# USB.net
KiCad netlist of a schematic drawn in Altium Designer
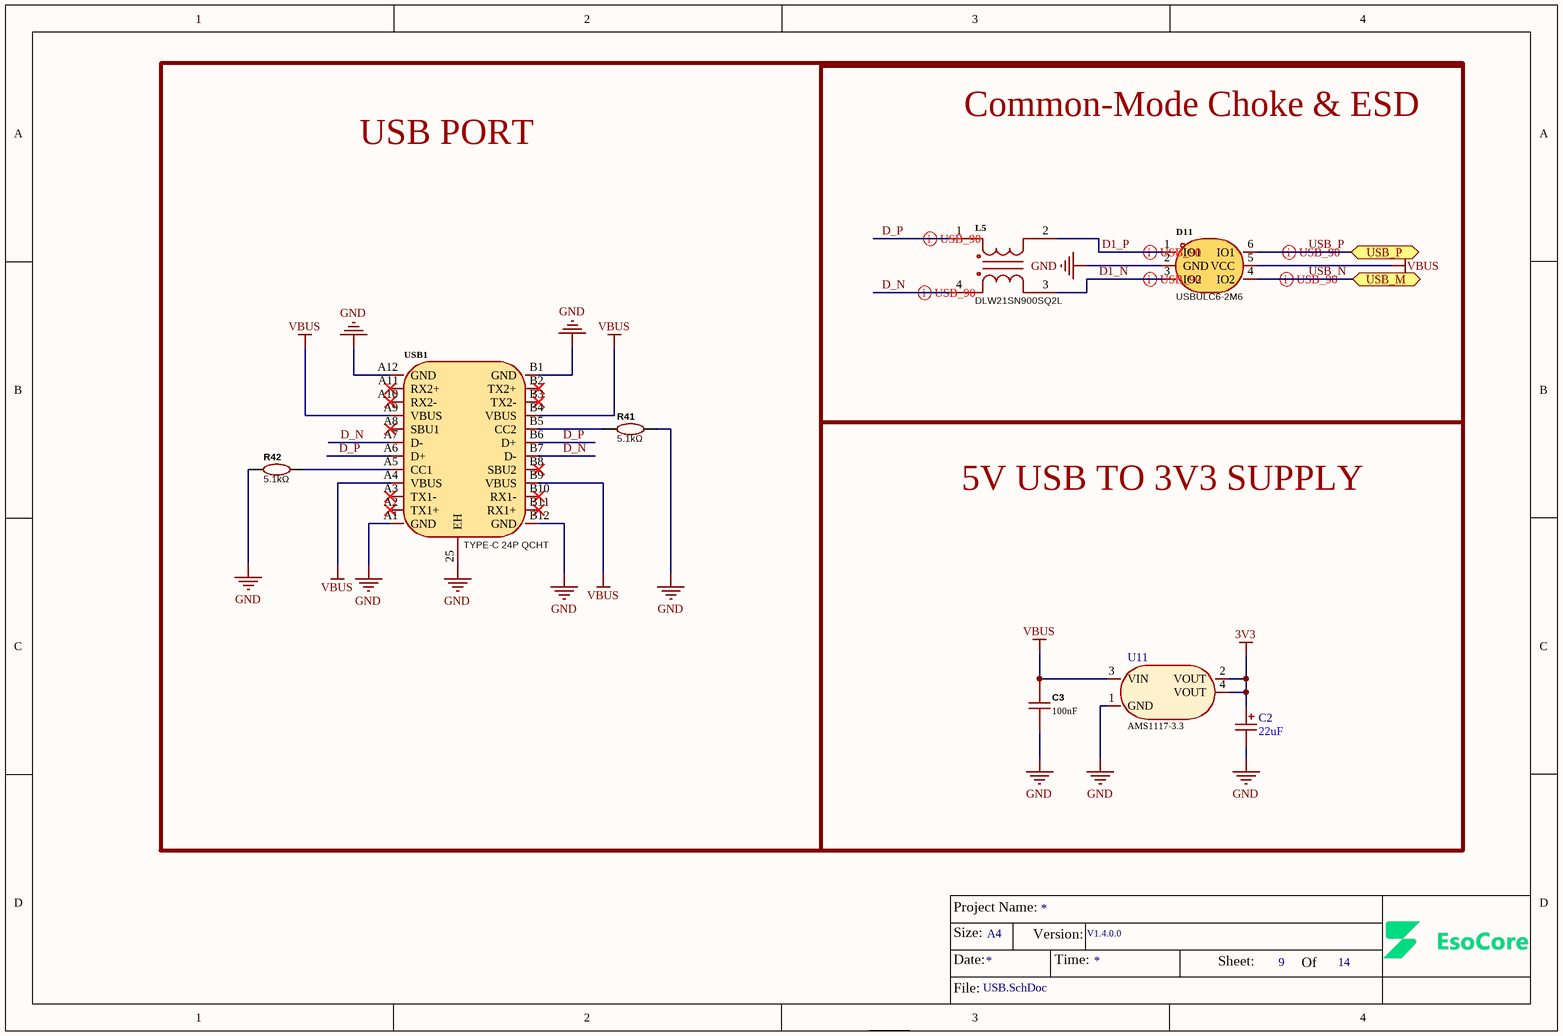
[diagram p0: USB.SchDoc]

(export (version "E")
  (design (tool "Eeschema 10.0.6"))
  (components
    (comp (ref "C2")
      (value "22uF")
      (footprint "CASE-A_3216")
      (fields
        (field (name "MANUFACTURER") "Kyocera AVX")
        (field (name "MANUFACTURER PART") "TAJA226K010RNJ")
        (field (name "TOLERANCE") "±10%")
      )
      (libsource (lib "altium-import") (part "root_1_TAJA226K010RNJ_"))
    )
    (comp (ref "C3")
      (value "100nF")
      (footprint "C_0603")
      (fields
        (field (name "MANUFACTURER") "YAGEO(国巨)")
        (field (name "MANUFACTURER PART") "CC0603KRX7R9BB104")
        (field (name "TOLERANCE") "±10%")
      )
      (libsource (lib "altium-import") (part "root_3_CC0603KRX7R9BB104_"))
    )
    (comp (ref "D11")
      (value "USBULC6-2M6")
      (footprint "SON-6_L1.4-W1.0-P0.50-TL_USBULC6-2M6")
      (fields (field (name "MANUFACTURER") "ST(意法半导体)"))
      (libsource (lib "EsoCore_Edge_Board_V1-0.0.0") (part "USBULC6-2M6"))
    )
    (comp (ref "L5")
      (value "DLW21SN900SQ2L")
      (footprint "FILTER-SMD_4P-L2.0-W1.2-BL_DLW21H")
      (fields (field (name "MANUFACTURER") "muRata(村田)"))
      (libsource (lib "EsoCore_Edge_Board_V1-0.0.0") (part "DLW21SN900SQ2L"))
    )
    (comp (ref "R41")
      (value "5.1kΩ")
      (footprint "R_0603")
      (fields (field (name "MANUFACTURER") "YAGEO(国巨)") (field (name "MANUFACTURER PART") "RC0603FR-075K1L"))
      (libsource (lib "altium-import") (part "root_0_5.1kΩ_"))
    )
    (comp (ref "R42")
      (value "5.1kΩ")
      (footprint "R_0603")
      (fields (field (name "MANUFACTURER") "YAGEO(国巨)") (field (name "MANUFACTURER PART") "RC0603FR-075K1L"))
      (libsource (lib "altium-import") (part "root_0_5.1kΩ_"))
    )
    (comp (ref "U11")
      (value "AMS1117-3.3")
      (footprint "SOT-223-3_L6.5-W3.4-P2.30-LS7.0-BR")
      (fields (field (name "MANUFACTURER") "AMS"))
      (libsource (lib "altium-import") (part "root_0_AMS1117-3.3_C6186_"))
    )
    (comp (ref "USB1")
      (value "TYPE-C 24P QCHT")
      (footprint "TYPE-C-SMD_TYPE-C-24P-QCHT")
      (fields (field (name "MANUFACTURER") "SHOU HAN(首韩)"))
      (libsource (lib "EsoCore_Edge_Board_V1-0.0.0") (part "TYPE-C 24P QCHT"))
    )
  )
  (nets
    (net (code "1") (name "/D1_N") (class "Default")
      (node (ref "D11") (pin "3") (pinfunction "IO2_3") (pintype "passive"))
      (node (ref "L5") (pin "3") (pinfunction "3_3") (pintype "passive"))
    )
    (net (code "2") (name "/D1_P") (class "Default")
      (node (ref "D11") (pin "1") (pinfunction "IO1_1") (pintype "passive"))
      (node (ref "L5") (pin "2") (pinfunction "2_2") (pintype "passive"))
    )
    (net (code "3") (name "/D_N") (class "Default")
      (node (ref "L5") (pin "4") (pinfunction "4_4") (pintype "passive"))
      (node (ref "USB1") (pin "A7") (pinfunction "D-_A7") (pintype "passive"))
      (node (ref "USB1") (pin "B7") (pinfunction "D-_B7") (pintype "passive"))
    )
    (net (code "4") (name "/D_P") (class "Default")
      (node (ref "L5") (pin "1") (pinfunction "1_1") (pintype "passive"))
      (node (ref "USB1") (pin "A6") (pinfunction "D+_A6") (pintype "passive"))
      (node (ref "USB1") (pin "B6") (pinfunction "D+_B6") (pintype "passive"))
    )
    (net (code "5") (name "/USB_N") (class "Default")
      (node (ref "D11") (pin "4") (pinfunction "IO2_4") (pintype "passive"))
    )
    (net (code "6") (name "/USB_P") (class "Default")
      (node (ref "D11") (pin "6") (pinfunction "IO1_6") (pintype "passive"))
    )
    (net (code "7") (name "3V3") (class "Default")
      (node (ref "C2") (pin "1") (pinfunction "1_1") (pintype "passive"))
      (node (ref "U11") (pin "2") (pinfunction "VOUT_2") (pintype "passive"))
      (node (ref "U11") (pin "4") (pinfunction "VOUT_4") (pintype "passive"))
    )
    (net (code "8") (name "GND") (class "Default")
      (node (ref "C2") (pin "2") (pinfunction "2_2") (pintype "passive"))
      (node (ref "C3") (pin "2") (pinfunction "2_2") (pintype "passive"))
      (node (ref "D11") (pin "2") (pinfunction "GND_2") (pintype "passive"))
      (node (ref "R41") (pin "2") (pinfunction "2_2") (pintype "passive"))
      (node (ref "R42") (pin "1") (pinfunction "1_1") (pintype "passive"))
      (node (ref "U11") (pin "1") (pinfunction "GND_1") (pintype "passive"))
      (node (ref "USB1") (pin "25") (pinfunction "EH_25") (pintype "passive"))
      (node (ref "USB1") (pin "A1") (pinfunction "GND_A1") (pintype "passive"))
      (node (ref "USB1") (pin "A12") (pinfunction "GND_A12") (pintype "passive"))
      (node (ref "USB1") (pin "B1") (pinfunction "GND_B1") (pintype "passive"))
      (node (ref "USB1") (pin "B12") (pinfunction "GND_B12") (pintype "passive"))
    )
    (net (code "9") (name "Net-(USB1-CC1)") (class "Default")
      (node (ref "R42") (pin "2") (pinfunction "2_2") (pintype "passive"))
      (node (ref "USB1") (pin "A5") (pinfunction "CC1_A5") (pintype "passive"))
    )
    (net (code "10") (name "Net-(USB1-CC2)") (class "Default")
      (node (ref "R41") (pin "1") (pinfunction "1_1") (pintype "passive"))
      (node (ref "USB1") (pin "B5") (pinfunction "CC2_B5") (pintype "passive"))
    )
    (net (code "11") (name "VBUS") (class "Default")
      (node (ref "C3") (pin "1") (pinfunction "1_1") (pintype "passive"))
      (node (ref "D11") (pin "5") (pinfunction "VCC_5") (pintype "passive"))
      (node (ref "U11") (pin "3") (pinfunction "VIN_3") (pintype "passive"))
      (node (ref "USB1") (pin "A4") (pinfunction "VBUS_A4") (pintype "passive"))
      (node (ref "USB1") (pin "A9") (pinfunction "VBUS_A9") (pintype "passive"))
      (node (ref "USB1") (pin "B4") (pinfunction "VBUS_B4") (pintype "passive"))
      (node (ref "USB1") (pin "B9") (pinfunction "VBUS_B9") (pintype "passive"))
    )
    (net (code "12") (name "unconnected-(USB1-RX1+-PadB11)") (class "Default")
      (node (ref "USB1") (pin "B11") (pinfunction "RX1+_B11") (pintype "passive+no_connect"))
    )
    (net (code "13") (name "unconnected-(USB1-RX1--PadB10)") (class "Default")
      (node (ref "USB1") (pin "B10") (pinfunction "RX1-_B10") (pintype "passive+no_connect"))
    )
    (net (code "14") (name "unconnected-(USB1-RX2+-PadA11)") (class "Default")
      (node (ref "USB1") (pin "A11") (pinfunction "RX2+_A11") (pintype "passive+no_connect"))
    )
    (net (code "15") (name "unconnected-(USB1-RX2--PadA10)") (class "Default")
      (node (ref "USB1") (pin "A10") (pinfunction "RX2-_A10") (pintype "passive+no_connect"))
    )
    (net (code "16") (name "unconnected-(USB1-SBU1-PadA8)") (class "Default")
      (node (ref "USB1") (pin "A8") (pinfunction "SBU1_A8") (pintype "passive+no_connect"))
    )
    (net (code "17") (name "unconnected-(USB1-SBU2-PadB8)") (class "Default")
      (node (ref "USB1") (pin "B8") (pinfunction "SBU2_B8") (pintype "passive+no_connect"))
    )
    (net (code "18") (name "unconnected-(USB1-TX1+-PadA2)") (class "Default")
      (node (ref "USB1") (pin "A2") (pinfunction "TX1+_A2") (pintype "passive+no_connect"))
    )
    (net (code "19") (name "unconnected-(USB1-TX1--PadA3)") (class "Default")
      (node (ref "USB1") (pin "A3") (pinfunction "TX1-_A3") (pintype "passive+no_connect"))
    )
    (net (code "20") (name "unconnected-(USB1-TX2+-PadB2)") (class "Default")
      (node (ref "USB1") (pin "B2") (pinfunction "TX2+_B2") (pintype "passive+no_connect"))
    )
    (net (code "21") (name "unconnected-(USB1-TX2--PadB3)") (class "Default")
      (node (ref "USB1") (pin "B3") (pinfunction "TX2-_B3") (pintype "passive+no_connect"))
    )
  )
)
